# RedFly-Shield_v13.net
KiCad netlist of a schematic drawn in EAGLE
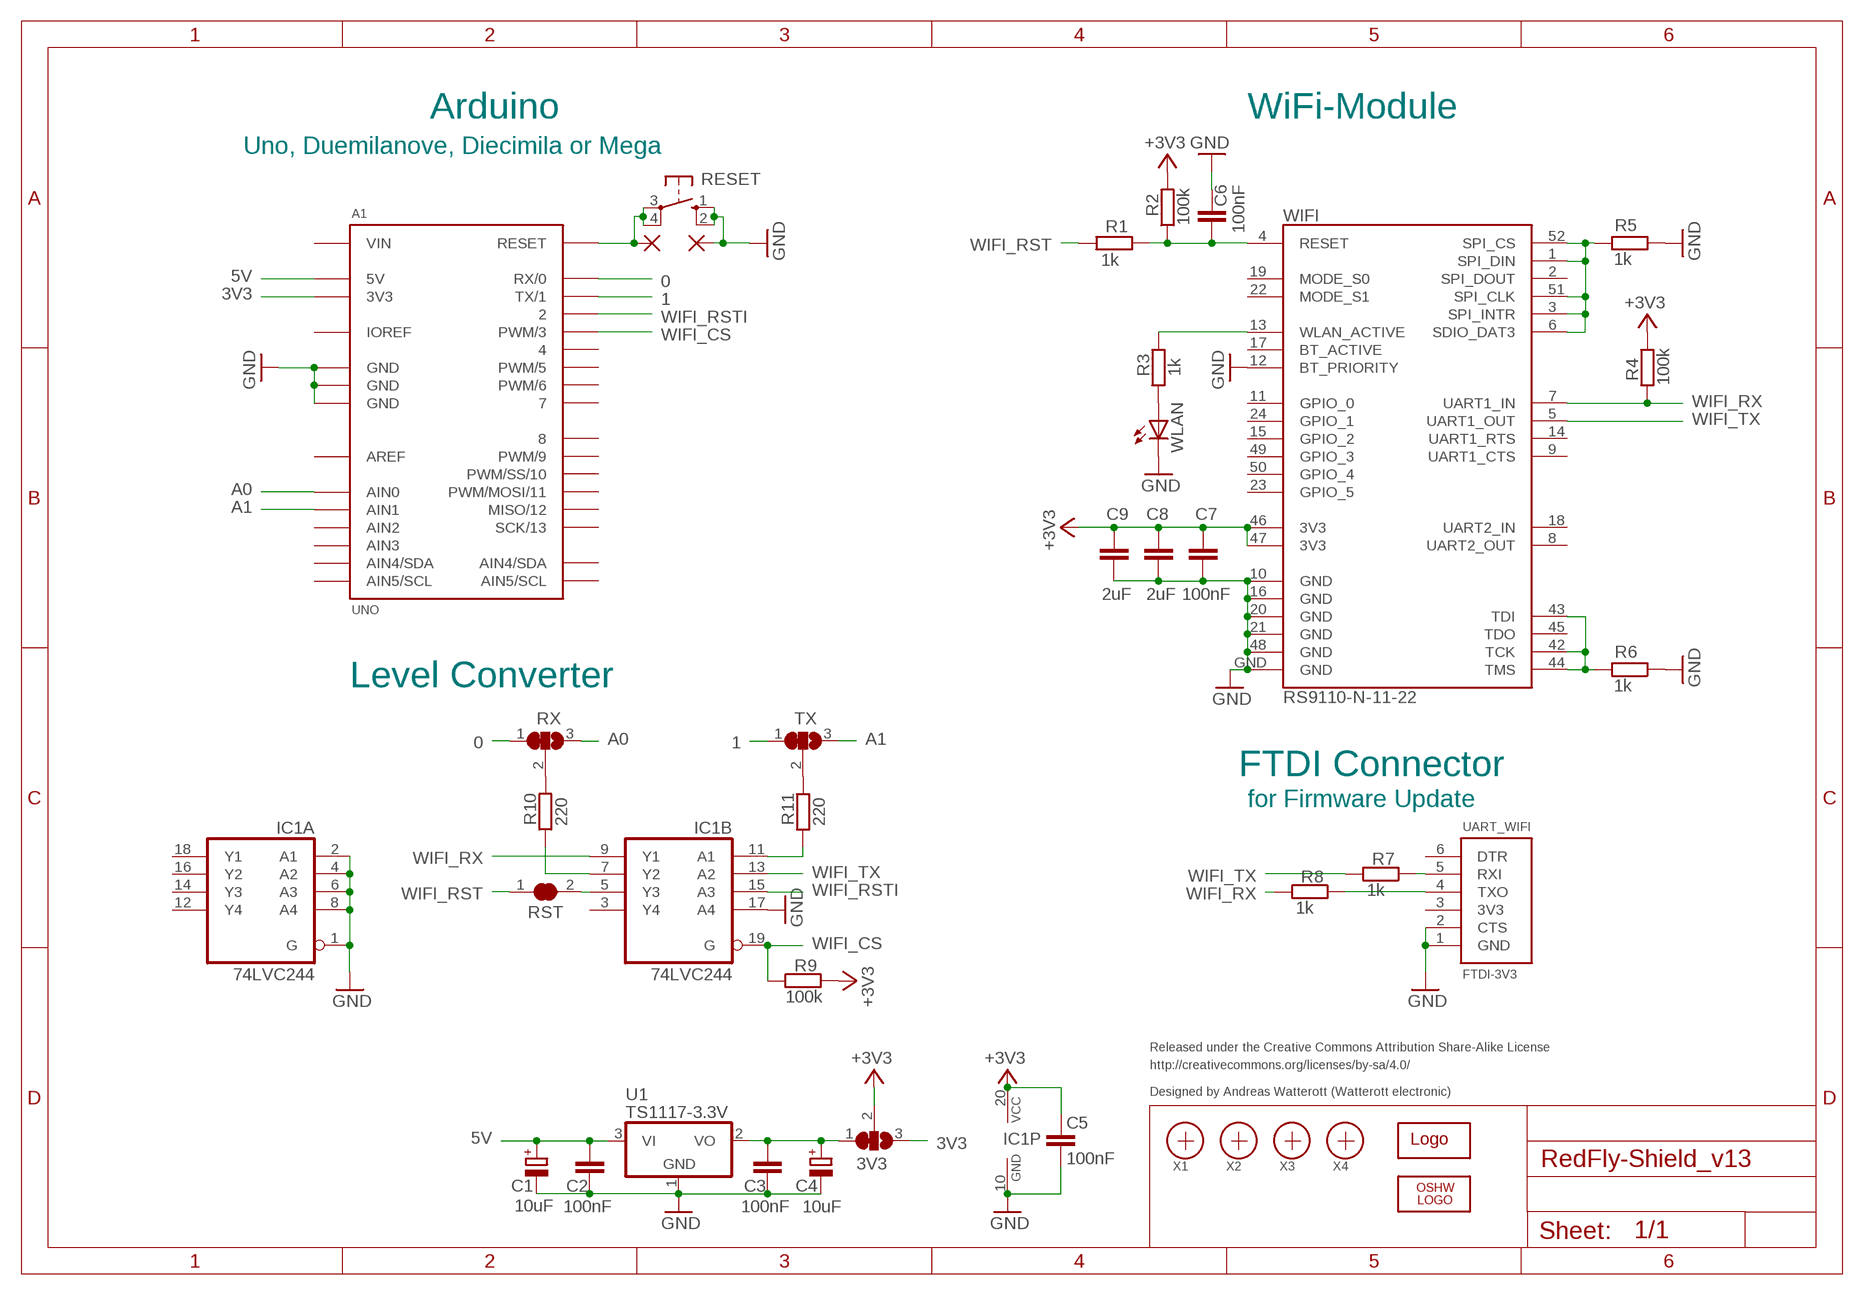
[diagram p0: schematic, sheet 1]

(export (version "E")
  (design (tool "Eeschema 10.0.6"))
  (components
    (comp (ref "3V3")
      (value "SJ2W")
      (footprint "eagle-import:SJ_2")
      (libsource (lib "eagle-import") (part "SJ2W"))
    )
    (comp (ref "A1")
      (value "UNO")
      (footprint "eagle-import:UNO")
      (libsource (lib "eagle-import") (part "UNO"))
    )
    (comp (ref "C1")
      (value "10uF")
      (footprint "eagle-import:153CLV-0505")
      (libsource (lib "eagle-import") (part "CPOL-EU153CLV-0505"))
    )
    (comp (ref "C2")
      (value "100nF")
      (footprint "eagle-import:C0603")
      (libsource (lib "eagle-import") (part "C-EUC0603"))
    )
    (comp (ref "C3")
      (value "100nF")
      (footprint "eagle-import:C0603")
      (libsource (lib "eagle-import") (part "C-EUC0603"))
    )
    (comp (ref "C4")
      (value "10uF")
      (footprint "eagle-import:153CLV-0505")
      (libsource (lib "eagle-import") (part "CPOL-EU153CLV-0505"))
    )
    (comp (ref "C5")
      (value "100nF")
      (footprint "eagle-import:C0603")
      (libsource (lib "eagle-import") (part "C-EUC0603"))
    )
    (comp (ref "C6")
      (value "100nF")
      (footprint "eagle-import:C0603")
      (libsource (lib "eagle-import") (part "C-EUC0603"))
    )
    (comp (ref "C7")
      (value "100nF")
      (footprint "eagle-import:C0603")
      (libsource (lib "eagle-import") (part "C-EUC0603"))
    )
    (comp (ref "C8")
      (value "2uF")
      (footprint "eagle-import:C0603")
      (libsource (lib "eagle-import") (part "C-EUC0603"))
    )
    (comp (ref "C9")
      (value "2uF")
      (footprint "eagle-import:C0603")
      (libsource (lib "eagle-import") (part "C-EUC0603"))
    )
    (comp (ref "GND")
      (value "SMD2")
      (footprint "eagle-import:SMD1,27-2,54")
      (libsource (lib "eagle-import") (part "SMD2"))
    )
    (comp (ref "IC1")
      (value "74LVC244")
      (footprint "eagle-import:SO20W")
      (libsource (lib "eagle-import") (part "74244DWHC"))
    )
    (comp (ref "LOGO1")
      (value "OSHW_LOGO_6MILX0100-NT")
      (footprint "eagle-import:OSHW_6X100_NOTEXT")
      (libsource (lib "eagle-import") (part "OSHW_LOGO_6MILX0100-NT"))
    )
    (comp (ref "R1")
      (value "1k")
      (footprint "eagle-import:R0603")
      (libsource (lib "eagle-import") (part "R-EU_R0603"))
    )
    (comp (ref "R2")
      (value "100k")
      (footprint "eagle-import:R0603")
      (libsource (lib "eagle-import") (part "R-EU_R0603"))
    )
    (comp (ref "R3")
      (value "1k")
      (footprint "eagle-import:R0603")
      (libsource (lib "eagle-import") (part "R-EU_R0603"))
    )
    (comp (ref "R4")
      (value "100k")
      (footprint "eagle-import:R0603")
      (libsource (lib "eagle-import") (part "R-EU_R0603"))
    )
    (comp (ref "R5")
      (value "1k")
      (footprint "eagle-import:R0603")
      (libsource (lib "eagle-import") (part "R-EU_R0603"))
    )
    (comp (ref "R6")
      (value "1k")
      (footprint "eagle-import:R0603")
      (libsource (lib "eagle-import") (part "R-EU_R0603"))
    )
    (comp (ref "R7")
      (value "1k")
      (footprint "eagle-import:R0603")
      (libsource (lib "eagle-import") (part "R-EU_R0603"))
    )
    (comp (ref "R8")
      (value "1k")
      (footprint "eagle-import:R0603")
      (libsource (lib "eagle-import") (part "R-EU_R0603"))
    )
    (comp (ref "R9")
      (value "100k")
      (footprint "eagle-import:R0603")
      (libsource (lib "eagle-import") (part "R-EU_R0603"))
    )
    (comp (ref "R10")
      (value "220")
      (footprint "eagle-import:R0603")
      (libsource (lib "eagle-import") (part "R-EU_R0603"))
    )
    (comp (ref "R11")
      (value "220")
      (footprint "eagle-import:R0603")
      (libsource (lib "eagle-import") (part "R-EU_R0603"))
    )
    (comp (ref "RESET")
      (value "10-XX")
      (footprint "eagle-import:B3F-10XX")
      (fields (field (name "MPN") "B3F-1000"))
      (libsource (lib "eagle-import") (part "10-XX"))
    )
    (comp (ref "RST") (value "SJ") (footprint "eagle-import:SJ") (libsource (lib "eagle-import") (part "SJ")))
    (comp (ref "RST2")
      (value "SMD2")
      (footprint "eagle-import:SMD1,27-2,54")
      (libsource (lib "eagle-import") (part "SMD2"))
    )
    (comp (ref "RX")
      (value "SJ2W")
      (footprint "eagle-import:SJ_2")
      (libsource (lib "eagle-import") (part "SJ2W"))
    )
    (comp (ref "TX")
      (value "SJ2W")
      (footprint "eagle-import:SJ_2")
      (libsource (lib "eagle-import") (part "SJ2W"))
    )
    (comp (ref "U$1")
      (value "WE-LOGO")
      (footprint "eagle-import:WE-LOGO")
      (libsource (lib "eagle-import") (part "WE-LOGO"))
    )
    (comp (ref "U1")
      (value "TS1117-3.3V")
      (footprint "eagle-import:SOT223")
      (libsource (lib "eagle-import") (part "TS1117"))
    )
    (comp (ref "UART_WIFI")
      (value "FTDI-3V3")
      (footprint "eagle-import:FTDI")
      (libsource (lib "eagle-import") (part "FTDI"))
    )
    (comp (ref "WIFI")
      (value "RS9110-N-11-22")
      (footprint "eagle-import:RS9110-N-11-21")
      (libsource (lib "eagle-import") (part "RS9110-N-11-21"))
    )
    (comp (ref "WLAN")
      (value "LEDCHIPLED_0603")
      (footprint "eagle-import:CHIPLED_0603")
      (libsource (lib "eagle-import") (part "LEDCHIPLED_0603"))
    )
    (comp (ref "X1")
      (value "PASSER")
      (footprint "eagle-import:PASSER")
      (libsource (lib "eagle-import") (part "PASSER"))
    )
    (comp (ref "X2")
      (value "PASSER")
      (footprint "eagle-import:PASSER")
      (libsource (lib "eagle-import") (part "PASSER"))
    )
    (comp (ref "X3")
      (value "PASSER")
      (footprint "eagle-import:PASSER")
      (libsource (lib "eagle-import") (part "PASSER"))
    )
    (comp (ref "X4")
      (value "PASSER")
      (footprint "eagle-import:PASSER")
      (libsource (lib "eagle-import") (part "PASSER"))
    )
  )
  (nets
    (net (code "1") (name "+3V3") (class "Default")
      (node (ref "3V3") (pin "2") (pinfunction "2_2") (pintype "passive"))
      (node (ref "C5") (pin "1") (pinfunction "1_1") (pintype "passive"))
      (node (ref "C7") (pin "1") (pinfunction "1_1") (pintype "passive"))
      (node (ref "C8") (pin "1") (pinfunction "1_1") (pintype "passive"))
      (node (ref "C9") (pin "1") (pinfunction "1_1") (pintype "passive"))
      (node (ref "IC1") (pin "20") (pinfunction "VCC_20") (pintype "power_in"))
      (node (ref "R2") (pin "2") (pinfunction "2_2") (pintype "passive"))
      (node (ref "R4") (pin "1") (pinfunction "1_1") (pintype "passive"))
      (node (ref "R9") (pin "2") (pinfunction "2_2") (pintype "passive"))
      (node (ref "WIFI") (pin "46") (pinfunction "3V3_46") (pintype "power_in"))
      (node (ref "WIFI") (pin "47") (pinfunction "3V3_47") (pintype "power_in"))
    )
    (net (code "2") (name "/0") (class "Default")
      (node (ref "A1") (pin "0") (pinfunction "RX/0_0") (pintype "bidirectional"))
      (node (ref "RX") (pin "1") (pinfunction "1_1") (pintype "passive"))
    )
    (net (code "3") (name "/1") (class "Default")
      (node (ref "A1") (pin "1") (pinfunction "TX/1_1") (pintype "bidirectional"))
      (node (ref "TX") (pin "1") (pinfunction "1_1") (pintype "passive"))
    )
    (net (code "4") (name "/3V3") (class "Default")
      (node (ref "3V3") (pin "3") (pinfunction "3_3") (pintype "passive"))
      (node (ref "A1") (pin "3V3") (pinfunction "3V3_3V3") (pintype "power_in"))
    )
    (net (code "5") (name "/5V") (class "Default")
      (node (ref "A1") (pin "5V") (pinfunction "5V_5V") (pintype "power_in"))
      (node (ref "C1") (pin "+") (pinfunction "+_+") (pintype "passive"))
      (node (ref "C2") (pin "1") (pinfunction "1_1") (pintype "passive"))
      (node (ref "U1") (pin "3") (pinfunction "VI_3") (pintype "input"))
    )
    (net (code "6") (name "/A0") (class "Default")
      (node (ref "A1") (pin "AIN0") (pinfunction "AIN0_AIN0") (pintype "bidirectional"))
      (node (ref "RX") (pin "3") (pinfunction "3_3") (pintype "passive"))
    )
    (net (code "7") (name "/A1") (class "Default")
      (node (ref "A1") (pin "AIN1") (pinfunction "AIN1_AIN1") (pintype "bidirectional"))
      (node (ref "TX") (pin "3") (pinfunction "3_3") (pintype "passive"))
    )
    (net (code "8") (name "/AREF") (class "Default")
      (node (ref "A1") (pin "AREF") (pinfunction "AREF_AREF") (pintype "power_in"))
    )
    (net (code "9") (name "/IOREF") (class "Default")
      (node (ref "A1") (pin "IOREF") (pinfunction "IOREF_IOREF") (pintype "power_in"))
    )
    (net (code "10") (name "/VIN") (class "Default")
      (node (ref "A1") (pin "VIN") (pinfunction "VIN_VIN") (pintype "power_in"))
    )
    (net (code "11") (name "/WIFI_CS") (class "Default")
      (node (ref "A1") (pin "3") (pinfunction "PWM/3_3") (pintype "bidirectional"))
      (node (ref "IC1") (pin "19") (pinfunction "G_19") (pintype "input"))
      (node (ref "R9") (pin "1") (pinfunction "1_1") (pintype "passive"))
    )
    (net (code "12") (name "/WIFI_RST") (class "Default")
      (node (ref "R1") (pin "2") (pinfunction "2_2") (pintype "passive"))
      (node (ref "RST") (pin "1") (pinfunction "1_1") (pintype "passive"))
    )
    (net (code "13") (name "/WIFI_RSTI") (class "Default")
      (node (ref "A1") (pin "2") (pinfunction "2_2") (pintype "bidirectional"))
      (node (ref "IC1") (pin "15") (pinfunction "A3_15") (pintype "input"))
    )
    (net (code "14") (name "/WIFI_RX") (class "Default")
      (node (ref "IC1") (pin "9") (pinfunction "Y1_9") (pintype "tri_state"))
      (node (ref "R4") (pin "2") (pinfunction "2_2") (pintype "passive"))
      (node (ref "R8") (pin "2") (pinfunction "2_2") (pintype "passive"))
      (node (ref "WIFI") (pin "7") (pinfunction "UART1_IN_7") (pintype "bidirectional"))
    )
    (net (code "15") (name "/WIFI_TX") (class "Default")
      (node (ref "IC1") (pin "13") (pinfunction "A2_13") (pintype "input"))
      (node (ref "R7") (pin "2") (pinfunction "2_2") (pintype "passive"))
      (node (ref "WIFI") (pin "5") (pinfunction "UART1_OUT_5") (pintype "bidirectional"))
    )
    (net (code "16") (name "GND") (class "Default")
      (node (ref "A1") (pin "GND@1") (pinfunction "GND_GND@1") (pintype "power_in"))
      (node (ref "A1") (pin "GND@2") (pinfunction "GND_GND@2") (pintype "power_in"))
      (node (ref "A1") (pin "GND@3") (pinfunction "GND_GND@3") (pintype "power_in"))
      (node (ref "C1") (pin "-") (pinfunction "-_-") (pintype "passive"))
      (node (ref "C2") (pin "2") (pinfunction "2_2") (pintype "passive"))
      (node (ref "C3") (pin "2") (pinfunction "2_2") (pintype "passive"))
      (node (ref "C4") (pin "-") (pinfunction "-_-") (pintype "passive"))
      (node (ref "C5") (pin "2") (pinfunction "2_2") (pintype "passive"))
      (node (ref "C6") (pin "1") (pinfunction "1_1") (pintype "passive"))
      (node (ref "C7") (pin "2") (pinfunction "2_2") (pintype "passive"))
      (node (ref "C8") (pin "2") (pinfunction "2_2") (pintype "passive"))
      (node (ref "C9") (pin "2") (pinfunction "2_2") (pintype "passive"))
      (node (ref "GND") (pin "1") (pinfunction "P_1") (pintype "passive"))
      (node (ref "IC1") (pin "1") (pinfunction "G_1") (pintype "input"))
      (node (ref "IC1") (pin "10") (pinfunction "GND_10") (pintype "power_in"))
      (node (ref "IC1") (pin "17") (pinfunction "A4_17") (pintype "input"))
      (node (ref "IC1") (pin "2") (pinfunction "A1_2") (pintype "input"))
      (node (ref "IC1") (pin "4") (pinfunction "A2_4") (pintype "input"))
      (node (ref "IC1") (pin "6") (pinfunction "A3_6") (pintype "input"))
      (node (ref "IC1") (pin "8") (pinfunction "A4_8") (pintype "input"))
      (node (ref "R5") (pin "1") (pinfunction "1_1") (pintype "passive"))
      (node (ref "R6") (pin "1") (pinfunction "1_1") (pintype "passive"))
      (node (ref "RESET") (pin "1") (pinfunction "S_1") (pintype "passive"))
      (node (ref "RESET") (pin "2") (pinfunction "S1_2") (pintype "passive"))
      (node (ref "U1") (pin "1") (pinfunction "GND_1") (pintype "passive"))
      (node (ref "UART_WIFI") (pin "1") (pinfunction "GND_1") (pintype "bidirectional"))
      (node (ref "UART_WIFI") (pin "2") (pinfunction "CTS_2") (pintype "bidirectional"))
      (node (ref "WIFI") (pin "10") (pinfunction "GND_10") (pintype "power_in"))
      (node (ref "WIFI") (pin "12") (pinfunction "BT_PRIORITY_12") (pintype "bidirectional"))
      (node (ref "WIFI") (pin "16") (pinfunction "GND_16") (pintype "power_in"))
      (node (ref "WIFI") (pin "20") (pinfunction "GND_20") (pintype "power_in"))
      (node (ref "WIFI") (pin "21") (pinfunction "GND_21") (pintype "power_in"))
      (node (ref "WIFI") (pin "48") (pinfunction "GND_48") (pintype "power_in"))
      (node (ref "WIFI") (pin "GND") (pinfunction "GND_GND") (pintype "power_in"))
      (node (ref "WLAN") (pin "C") (pinfunction "C_C") (pintype "passive"))
    )
    (net (code "17") (name "Net-(A1-RESET)") (class "Default")
      (node (ref "A1") (pin "RST") (pinfunction "RESET_RST") (pintype "bidirectional"))
      (node (ref "RESET") (pin "3") (pinfunction "P_3") (pintype "passive"))
      (node (ref "RESET") (pin "4") (pinfunction "P1_4") (pintype "passive"))
      (node (ref "RST2") (pin "1") (pinfunction "P_1") (pintype "passive"))
    )
    (net (code "18") (name "Net-(IC1B-A1)") (class "Default")
      (node (ref "IC1") (pin "11") (pinfunction "A1_11") (pintype "input"))
      (node (ref "R11") (pin "2") (pinfunction "2_2") (pintype "passive"))
    )
    (net (code "19") (name "Net-(IC1B-Y2)") (class "Default")
      (node (ref "IC1") (pin "7") (pinfunction "Y2_7") (pintype "tri_state"))
      (node (ref "R10") (pin "1") (pinfunction "1_1") (pintype "passive"))
    )
    (net (code "20") (name "Net-(IC1B-Y3)") (class "Default")
      (node (ref "IC1") (pin "5") (pinfunction "Y3_5") (pintype "tri_state"))
      (node (ref "RST") (pin "2") (pinfunction "2_2") (pintype "passive"))
    )
    (net (code "21") (name "Net-(R3-Pad2)") (class "Default")
      (node (ref "R3") (pin "2") (pinfunction "2_2") (pintype "passive"))
      (node (ref "WLAN") (pin "A") (pinfunction "A_A") (pintype "passive"))
    )
    (net (code "22") (name "Net-(R10-Pad2)") (class "Default")
      (node (ref "R10") (pin "2") (pinfunction "2_2") (pintype "passive"))
      (node (ref "RX") (pin "2") (pinfunction "2_2") (pintype "passive"))
    )
    (net (code "23") (name "Net-(R11-Pad1)") (class "Default")
      (node (ref "R11") (pin "1") (pinfunction "1_1") (pintype "passive"))
      (node (ref "TX") (pin "2") (pinfunction "2_2") (pintype "passive"))
    )
    (net (code "24") (name "Net-(U1-VO)") (class "Default")
      (node (ref "3V3") (pin "1") (pinfunction "1_1") (pintype "passive"))
      (node (ref "C3") (pin "1") (pinfunction "1_1") (pintype "passive"))
      (node (ref "C4") (pin "+") (pinfunction "+_+") (pintype "passive"))
      (node (ref "U1") (pin "2") (pinfunction "VO_2") (pintype "passive"))
    )
    (net (code "25") (name "Net-(UART_WIFI-RXI)") (class "Default")
      (node (ref "R7") (pin "1") (pinfunction "1_1") (pintype "passive"))
      (node (ref "UART_WIFI") (pin "5") (pinfunction "RXI_5") (pintype "bidirectional"))
    )
    (net (code "26") (name "Net-(UART_WIFI-TXO)") (class "Default")
      (node (ref "R8") (pin "1") (pinfunction "1_1") (pintype "passive"))
      (node (ref "UART_WIFI") (pin "4") (pinfunction "TXO_4") (pintype "bidirectional"))
    )
    (net (code "27") (name "Net-(WIFI-RESET)") (class "Default")
      (node (ref "C6") (pin "2") (pinfunction "2_2") (pintype "passive"))
      (node (ref "R1") (pin "1") (pinfunction "1_1") (pintype "passive"))
      (node (ref "R2") (pin "1") (pinfunction "1_1") (pintype "passive"))
      (node (ref "WIFI") (pin "4") (pinfunction "RESET_4") (pintype "bidirectional"))
    )
    (net (code "28") (name "Net-(WIFI-SDIO_DAT3)") (class "Default")
      (node (ref "R5") (pin "2") (pinfunction "2_2") (pintype "passive"))
      (node (ref "WIFI") (pin "1") (pinfunction "SPI_DIN_1") (pintype "bidirectional"))
      (node (ref "WIFI") (pin "3") (pinfunction "SPI_INTR_3") (pintype "bidirectional"))
      (node (ref "WIFI") (pin "51") (pinfunction "SPI_CLK_51") (pintype "bidirectional"))
      (node (ref "WIFI") (pin "52") (pinfunction "SPI_CS_52") (pintype "bidirectional"))
      (node (ref "WIFI") (pin "6") (pinfunction "SDIO_DAT3_6") (pintype "bidirectional"))
    )
    (net (code "29") (name "Net-(WIFI-TCK)") (class "Default")
      (node (ref "R6") (pin "2") (pinfunction "2_2") (pintype "passive"))
      (node (ref "WIFI") (pin "42") (pinfunction "TCK_42") (pintype "bidirectional"))
      (node (ref "WIFI") (pin "43") (pinfunction "TDI_43") (pintype "bidirectional"))
      (node (ref "WIFI") (pin "44") (pinfunction "TMS_44") (pintype "bidirectional"))
    )
    (net (code "30") (name "Net-(WIFI-WLAN_ACTIVE)") (class "Default")
      (node (ref "R3") (pin "1") (pinfunction "1_1") (pintype "passive"))
      (node (ref "WIFI") (pin "13") (pinfunction "WLAN_ACTIVE_13") (pintype "bidirectional"))
    )
    (net (code "31") (name "unconnected-(A1-AIN4{slash}SDA-PadAIN4)") (class "Default")
      (node (ref "A1") (pin "AIN4") (pinfunction "AIN4/SDA_AIN4") (pintype "bidirectional"))
    )
    (net (code "32") (name "unconnected-(A1-AIN4{slash}SDA-PadSDA)") (class "Default")
      (node (ref "A1") (pin "SDA") (pinfunction "AIN4/SDA_SDA") (pintype "bidirectional"))
    )
    (net (code "33") (name "unconnected-(A1-AIN5{slash}SCL-PadAIN5)") (class "Default")
      (node (ref "A1") (pin "AIN5") (pinfunction "AIN5/SCL_AIN5") (pintype "bidirectional"))
    )
    (net (code "34") (name "unconnected-(A1-AIN5{slash}SCL-PadSCL)") (class "Default")
      (node (ref "A1") (pin "SCL") (pinfunction "AIN5/SCL_SCL") (pintype "bidirectional"))
    )
    (net (code "35") (name "unconnected-(A1-MISO{slash}12-Pad12)") (class "Default")
      (node (ref "A1") (pin "12") (pinfunction "MISO/12_12") (pintype "bidirectional"))
    )
    (net (code "36") (name "unconnected-(A1-PWM{slash}5-Pad5)") (class "Default")
      (node (ref "A1") (pin "5") (pinfunction "PWM/5_5") (pintype "bidirectional"))
    )
    (net (code "37") (name "unconnected-(A1-PWM{slash}6-Pad6)") (class "Default")
      (node (ref "A1") (pin "6") (pinfunction "PWM/6_6") (pintype "bidirectional"))
    )
    (net (code "38") (name "unconnected-(A1-PWM{slash}9-Pad9)") (class "Default")
      (node (ref "A1") (pin "9") (pinfunction "PWM/9_9") (pintype "bidirectional"))
    )
    (net (code "39") (name "unconnected-(A1-PWM{slash}MOSI{slash}11-Pad11)") (class "Default")
      (node (ref "A1") (pin "11") (pinfunction "PWM/MOSI/11_11") (pintype "bidirectional"))
    )
    (net (code "40") (name "unconnected-(A1-PWM{slash}SS{slash}10-Pad10)") (class "Default")
      (node (ref "A1") (pin "10") (pinfunction "PWM/SS/10_10") (pintype "bidirectional"))
    )
    (net (code "41") (name "unconnected-(A1-Pad4)") (class "Default")
      (node (ref "A1") (pin "4") (pinfunction "4_4") (pintype "bidirectional"))
    )
    (net (code "42") (name "unconnected-(A1-Pad7)") (class "Default")
      (node (ref "A1") (pin "7") (pinfunction "7_7") (pintype "bidirectional"))
    )
    (net (code "43") (name "unconnected-(A1-Pad8)") (class "Default")
      (node (ref "A1") (pin "8") (pinfunction "8_8") (pintype "bidirectional"))
    )
    (net (code "44") (name "unconnected-(A1-PadAIN2)") (class "Default")
      (node (ref "A1") (pin "AIN2") (pinfunction "AIN2_AIN2") (pintype "bidirectional"))
    )
    (net (code "45") (name "unconnected-(A1-PadAIN3)") (class "Default")
      (node (ref "A1") (pin "AIN3") (pinfunction "AIN3_AIN3") (pintype "bidirectional"))
    )
    (net (code "46") (name "unconnected-(A1-SCK{slash}13-Pad13)") (class "Default")
      (node (ref "A1") (pin "13") (pinfunction "SCK/13_13") (pintype "bidirectional"))
    )
    (net (code "47") (name "unconnected-(IC1A-Y1-Pad18)") (class "Default")
      (node (ref "IC1") (pin "18") (pinfunction "Y1_18") (pintype "tri_state"))
    )
    (net (code "48") (name "unconnected-(IC1A-Y2-Pad16)") (class "Default")
      (node (ref "IC1") (pin "16") (pinfunction "Y2_16") (pintype "tri_state"))
    )
    (net (code "49") (name "unconnected-(IC1A-Y3-Pad14)") (class "Default")
      (node (ref "IC1") (pin "14") (pinfunction "Y3_14") (pintype "tri_state"))
    )
    (net (code "50") (name "unconnected-(IC1A-Y4-Pad12)") (class "Default")
      (node (ref "IC1") (pin "12") (pinfunction "Y4_12") (pintype "tri_state"))
    )
    (net (code "51") (name "unconnected-(IC1B-Y4-Pad3)") (class "Default")
      (node (ref "IC1") (pin "3") (pinfunction "Y4_3") (pintype "tri_state"))
    )
    (net (code "52") (name "unconnected-(UART_WIFI-3V3-Pad3)") (class "Default")
      (node (ref "UART_WIFI") (pin "3") (pinfunction "3V3_3") (pintype "bidirectional"))
    )
    (net (code "53") (name "unconnected-(UART_WIFI-DTR-Pad6)") (class "Default")
      (node (ref "UART_WIFI") (pin "6") (pinfunction "DTR_6") (pintype "bidirectional"))
    )
    (net (code "54") (name "unconnected-(WIFI-BT_ACTIVE-Pad17)") (class "Default")
      (node (ref "WIFI") (pin "17") (pinfunction "BT_ACTIVE_17") (pintype "bidirectional"))
    )
    (net (code "55") (name "unconnected-(WIFI-GPIO_0-Pad11)") (class "Default")
      (node (ref "WIFI") (pin "11") (pinfunction "GPIO_0_11") (pintype "bidirectional"))
    )
    (net (code "56") (name "unconnected-(WIFI-GPIO_1-Pad24)") (class "Default")
      (node (ref "WIFI") (pin "24") (pinfunction "GPIO_1_24") (pintype "bidirectional"))
    )
    (net (code "57") (name "unconnected-(WIFI-GPIO_2-Pad15)") (class "Default")
      (node (ref "WIFI") (pin "15") (pinfunction "GPIO_2_15") (pintype "bidirectional"))
    )
    (net (code "58") (name "unconnected-(WIFI-GPIO_3-Pad49)") (class "Default")
      (node (ref "WIFI") (pin "49") (pinfunction "GPIO_3_49") (pintype "bidirectional"))
    )
    (net (code "59") (name "unconnected-(WIFI-GPIO_4-Pad50)") (class "Default")
      (node (ref "WIFI") (pin "50") (pinfunction "GPIO_4_50") (pintype "bidirectional"))
    )
    (net (code "60") (name "unconnected-(WIFI-GPIO_5-Pad23)") (class "Default")
      (node (ref "WIFI") (pin "23") (pinfunction "GPIO_5_23") (pintype "bidirectional"))
    )
    (net (code "61") (name "unconnected-(WIFI-MODE_S0-Pad19)") (class "Default")
      (node (ref "WIFI") (pin "19") (pinfunction "MODE_S0_19") (pintype "bidirectional"))
    )
    (net (code "62") (name "unconnected-(WIFI-MODE_S1-Pad22)") (class "Default")
      (node (ref "WIFI") (pin "22") (pinfunction "MODE_S1_22") (pintype "bidirectional"))
    )
    (net (code "63") (name "unconnected-(WIFI-SPI_DOUT-Pad2)") (class "Default")
      (node (ref "WIFI") (pin "2") (pinfunction "SPI_DOUT_2") (pintype "bidirectional"))
    )
    (net (code "64") (name "unconnected-(WIFI-TDO-Pad45)") (class "Default")
      (node (ref "WIFI") (pin "45") (pinfunction "TDO_45") (pintype "bidirectional"))
    )
    (net (code "65") (name "unconnected-(WIFI-UART1_CTS-Pad9)") (class "Default")
      (node (ref "WIFI") (pin "9") (pinfunction "UART1_CTS_9") (pintype "bidirectional"))
    )
    (net (code "66") (name "unconnected-(WIFI-UART1_RTS-Pad14)") (class "Default")
      (node (ref "WIFI") (pin "14") (pinfunction "UART1_RTS_14") (pintype "bidirectional"))
    )
    (net (code "67") (name "unconnected-(WIFI-UART2_IN-Pad18)") (class "Default")
      (node (ref "WIFI") (pin "18") (pinfunction "UART2_IN_18") (pintype "bidirectional"))
    )
    (net (code "68") (name "unconnected-(WIFI-UART2_OUT-Pad8)") (class "Default")
      (node (ref "WIFI") (pin "8") (pinfunction "UART2_OUT_8") (pintype "bidirectional"))
    )
  )
)
